# Power_supply_CAN.net
KiCad netlist of a schematic drawn in Altium Designer
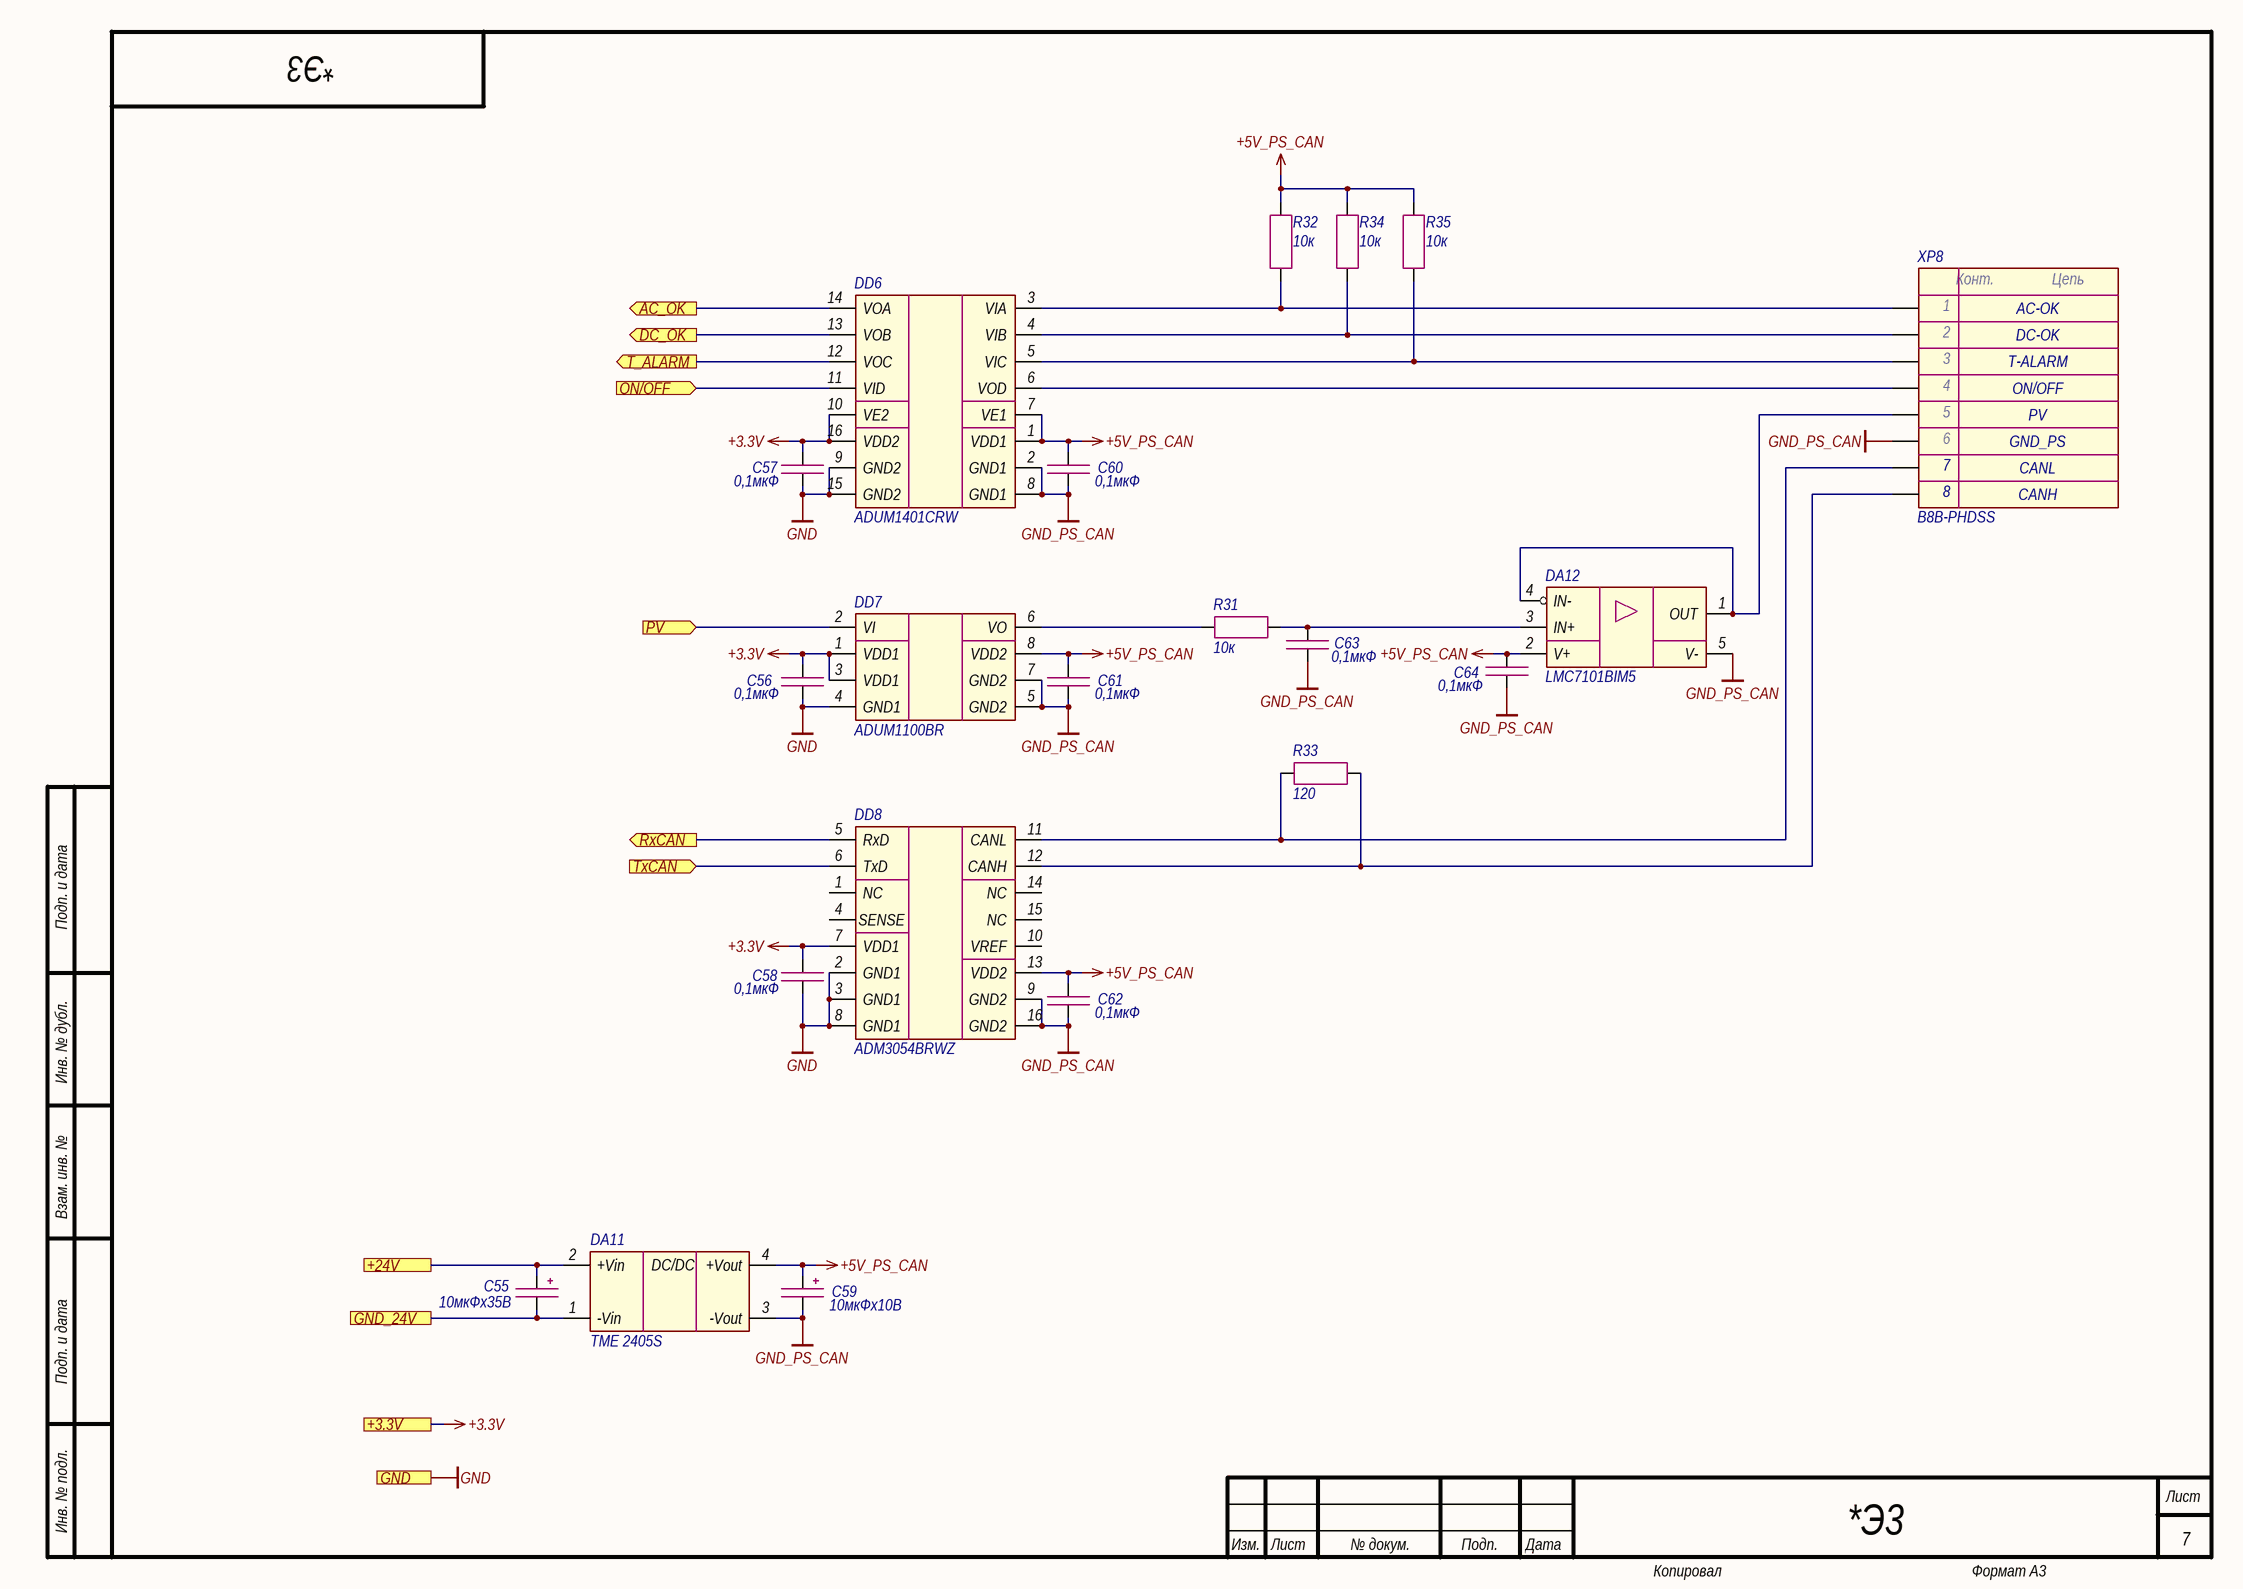
[diagram p0: Power_supply_CAN.SchDoc]

(export (version "E")
  (design (tool "Eeschema 10.0.6"))
  (components
    (comp (ref "C55")
      (value "10мкФх35B")
      (footprint "Pcb_library:CAP_C")
      (libsource (lib "Schem_library") (part "Capacitor_Polar"))
    )
    (comp (ref "C56")
      (value "0,1мкФ")
      (footprint "Pcb_library:CAP_0603")
      (fields (field (name "MANUFACTURER") "Murata"))
      (libsource (lib "Schem_library") (part "Capacitor"))
    )
    (comp (ref "C57")
      (value "0,1мкФ")
      (footprint "Pcb_library:CAP_0603")
      (fields (field (name "MANUFACTURER") "Murata"))
      (libsource (lib "Schem_library") (part "Capacitor"))
    )
    (comp (ref "C58")
      (value "0,1мкФ")
      (footprint "Pcb_library:CAP_0603")
      (fields (field (name "MANUFACTURER") "Murata"))
      (libsource (lib "Schem_library") (part "Capacitor"))
    )
    (comp (ref "C59")
      (value "10мкФх10B")
      (footprint "Pcb_library:CAP_A")
      (libsource (lib "Schem_library") (part "Capacitor_Polar"))
    )
    (comp (ref "C60")
      (value "0,1мкФ")
      (footprint "Pcb_library:CAP_0603")
      (fields (field (name "MANUFACTURER") "Murata"))
      (libsource (lib "Schem_library") (part "Capacitor"))
    )
    (comp (ref "C61")
      (value "0,1мкФ")
      (footprint "Pcb_library:CAP_0603")
      (fields (field (name "MANUFACTURER") "Murata"))
      (libsource (lib "Schem_library") (part "Capacitor"))
    )
    (comp (ref "C62")
      (value "0,1мкФ")
      (footprint "Pcb_library:CAP_0603")
      (fields (field (name "MANUFACTURER") "Murata"))
      (libsource (lib "Schem_library") (part "Capacitor"))
    )
    (comp (ref "C63")
      (value "0,1мкФ")
      (footprint "Pcb_library:CAP_0603")
      (fields (field (name "MANUFACTURER") "Murata"))
      (libsource (lib "Schem_library") (part "Capacitor"))
    )
    (comp (ref "C64")
      (value "0,1мкФ")
      (footprint "Pcb_library:CAP_0603")
      (fields (field (name "MANUFACTURER") "Murata"))
      (libsource (lib "Schem_library") (part "Capacitor"))
    )
    (comp (ref "DA11")
      (value "TME 2405S")
      (footprint "Pcb_library:TME (SIP-4)")
      (fields (field (name "MANUFACTURER") "Traco Power"))
      (libsource (lib "Schem_library") (part "TME"))
    )
    (comp (ref "DA12")
      (value "LMC7101BIM5")
      (footprint "Pcb_library:SOT-23-5")
      (fields (field (name "MANUFACTURER") "Texas Instruments"))
      (libsource (lib "Schem_library") (part "LMC7101"))
    )
    (comp (ref "DD6")
      (value "ADUM1401CRW")
      (footprint "Pcb_library:SOIC-16W")
      (fields (field (name "MANUFACTURER") "Analog Devices"))
      (libsource (lib "Schem_library") (part "ADUM1401"))
    )
    (comp (ref "DD7")
      (value "ADUM1100BR")
      (footprint "Pcb_library:SOIC-8")
      (fields (field (name "MANUFACTURER") "Analog Devices"))
      (libsource (lib "Schem_library") (part "ADUM1100"))
    )
    (comp (ref "DD8")
      (value "ADM3054BRWZ")
      (footprint "Pcb_library:SOIC-16W")
      (fields (field (name "MANUFACTURER") "Analog Devices"))
      (libsource (lib "Schem_library") (part "ADM3054BRWZ"))
    )
    (comp (ref "R31")
      (value "10к")
      (footprint "Pcb_library:RES_0603")
      (fields (field (name "MANUFACTURER") "Yageo"))
      (libsource (lib "Schem_library") (part "Resistor"))
    )
    (comp (ref "R32")
      (value "10к")
      (footprint "Pcb_library:RES_0603")
      (fields (field (name "MANUFACTURER") "Yageo"))
      (libsource (lib "Schem_library") (part "Resistor"))
    )
    (comp (ref "R33")
      (value "120")
      (footprint "Pcb_library:RES_0805")
      (fields (field (name "MANUFACTURER") "Yageo"))
      (libsource (lib "Schem_library") (part "Resistor"))
    )
    (comp (ref "R34")
      (value "10к")
      (footprint "Pcb_library:RES_0603")
      (fields (field (name "MANUFACTURER") "Yageo"))
      (libsource (lib "Schem_library") (part "Resistor"))
    )
    (comp (ref "R35")
      (value "10к")
      (footprint "Pcb_library:RES_0603")
      (fields (field (name "MANUFACTURER") "Yageo"))
      (libsource (lib "Schem_library") (part "Resistor"))
    )
    (comp (ref "XP8")
      (value "B8B-PHDSS")
      (footprint "Pcb_library:B8B-PHDSS")
      (fields (field (name "MANUFACTURER") "JST"))
      (libsource (lib "Schem_library") (part "Connector-8"))
    )
  )
  (nets
    (net (code "1") (name "+3.3V") (class "Default")
      (node (ref "C56") (pin "1") (pinfunction "1_1") (pintype "passive"))
      (node (ref "C57") (pin "1") (pinfunction "1_1") (pintype "passive"))
      (node (ref "C58") (pin "1") (pinfunction "1_1") (pintype "passive"))
      (node (ref "DD6") (pin "10") (pinfunction "VE2_10") (pintype "passive"))
      (node (ref "DD6") (pin "16") (pinfunction "VDD2_16") (pintype "passive"))
      (node (ref "DD7") (pin "1") (pinfunction "VDD1_1") (pintype "passive"))
      (node (ref "DD7") (pin "3") (pinfunction "VDD1_3") (pintype "passive"))
      (node (ref "DD8") (pin "7") (pinfunction "VDD1_7") (pintype "passive"))
    )
    (net (code "2") (name "+5V_PS_CAN") (class "Default")
      (node (ref "C59") (pin "1") (pinfunction "1_1") (pintype "passive"))
      (node (ref "C60") (pin "1") (pinfunction "1_1") (pintype "passive"))
      (node (ref "C61") (pin "1") (pinfunction "1_1") (pintype "passive"))
      (node (ref "C62") (pin "1") (pinfunction "1_1") (pintype "passive"))
      (node (ref "C64") (pin "1") (pinfunction "1_1") (pintype "passive"))
      (node (ref "DA11") (pin "4") (pinfunction "+Vout_4") (pintype "passive"))
      (node (ref "DA12") (pin "2") (pinfunction "V+_2") (pintype "passive"))
      (node (ref "DD6") (pin "1") (pinfunction "VDD1_1") (pintype "passive"))
      (node (ref "DD6") (pin "7") (pinfunction "VE1_7") (pintype "passive"))
      (node (ref "DD7") (pin "8") (pinfunction "VDD2_8") (pintype "passive"))
      (node (ref "DD8") (pin "13") (pinfunction "VDD2_13") (pintype "passive"))
      (node (ref "R32") (pin "1") (pinfunction "1_1") (pintype "passive"))
      (node (ref "R34") (pin "1") (pinfunction "1_1") (pintype "passive"))
      (node (ref "R35") (pin "1") (pinfunction "1_1") (pintype "passive"))
    )
    (net (code "3") (name "/+24V") (class "Default")
      (node (ref "C55") (pin "1") (pinfunction "1_1") (pintype "passive"))
      (node (ref "DA11") (pin "2") (pinfunction "+Vin_2") (pintype "passive"))
    )
    (net (code "4") (name "/AC_OK") (class "Default")
      (node (ref "DD6") (pin "14") (pinfunction "VOA_14") (pintype "passive"))
    )
    (net (code "5") (name "/DC_OK") (class "Default")
      (node (ref "DD6") (pin "13") (pinfunction "VOB_13") (pintype "passive"))
    )
    (net (code "6") (name "/GND_24V") (class "Default")
      (node (ref "C55") (pin "2") (pinfunction "2_2") (pintype "passive"))
      (node (ref "DA11") (pin "1") (pinfunction "-Vin_1") (pintype "passive"))
    )
    (net (code "7") (name "/ON{slash}OFF") (class "Default")
      (node (ref "DD6") (pin "11") (pinfunction "VID_11") (pintype "passive"))
    )
    (net (code "8") (name "/PV") (class "Default")
      (node (ref "DD7") (pin "2") (pinfunction "VI_2") (pintype "passive"))
    )
    (net (code "9") (name "/RxCAN") (class "Default")
      (node (ref "DD8") (pin "5") (pinfunction "RxD_5") (pintype "passive"))
    )
    (net (code "10") (name "/T_ALARM") (class "Default")
      (node (ref "DD6") (pin "12") (pinfunction "VOC_12") (pintype "passive"))
    )
    (net (code "11") (name "/TxCAN") (class "Default")
      (node (ref "DD8") (pin "6") (pinfunction "TxD_6") (pintype "passive"))
    )
    (net (code "12") (name "GND") (class "Default")
      (node (ref "C56") (pin "2") (pinfunction "2_2") (pintype "passive"))
      (node (ref "C57") (pin "2") (pinfunction "2_2") (pintype "passive"))
      (node (ref "C58") (pin "2") (pinfunction "2_2") (pintype "passive"))
      (node (ref "DD6") (pin "15") (pinfunction "GND2_15") (pintype "passive"))
      (node (ref "DD6") (pin "9") (pinfunction "GND2_9") (pintype "passive"))
      (node (ref "DD7") (pin "4") (pinfunction "GND1_4") (pintype "passive"))
      (node (ref "DD8") (pin "2") (pinfunction "GND1_2") (pintype "passive"))
      (node (ref "DD8") (pin "3") (pinfunction "GND1_3") (pintype "passive"))
      (node (ref "DD8") (pin "8") (pinfunction "GND1_8") (pintype "passive"))
    )
    (net (code "13") (name "GND_PS_CAN") (class "Default")
      (node (ref "C59") (pin "2") (pinfunction "2_2") (pintype "passive"))
      (node (ref "C60") (pin "2") (pinfunction "2_2") (pintype "passive"))
      (node (ref "C61") (pin "2") (pinfunction "2_2") (pintype "passive"))
      (node (ref "C62") (pin "2") (pinfunction "2_2") (pintype "passive"))
      (node (ref "C63") (pin "2") (pinfunction "2_2") (pintype "passive"))
      (node (ref "C64") (pin "2") (pinfunction "2_2") (pintype "passive"))
      (node (ref "DA11") (pin "3") (pinfunction "-Vout_3") (pintype "passive"))
      (node (ref "DA12") (pin "5") (pinfunction "V-_5") (pintype "passive"))
      (node (ref "DD6") (pin "2") (pinfunction "GND1_2") (pintype "passive"))
      (node (ref "DD6") (pin "8") (pinfunction "GND1_8") (pintype "passive"))
      (node (ref "DD7") (pin "5") (pinfunction "GND2_5") (pintype "passive"))
      (node (ref "DD7") (pin "7") (pinfunction "GND2_7") (pintype "passive"))
      (node (ref "DD8") (pin "16") (pinfunction "GND2_16") (pintype "passive"))
      (node (ref "DD8") (pin "9") (pinfunction "GND2_9") (pintype "passive"))
      (node (ref "XP8") (pin "6") (pintype "passive"))
    )
    (net (code "14") (name "Net-(DA12-IN+)") (class "Default")
      (node (ref "C63") (pin "1") (pinfunction "1_1") (pintype "passive"))
      (node (ref "DA12") (pin "3") (pinfunction "IN+_3") (pintype "passive"))
      (node (ref "R31") (pin "2") (pinfunction "2_2") (pintype "passive"))
    )
    (net (code "15") (name "Net-(DA12-IN-)") (class "Default")
      (node (ref "DA12") (pin "1") (pinfunction "OUT_1") (pintype "passive"))
      (node (ref "DA12") (pin "4") (pinfunction "IN-_4") (pintype "passive"))
      (node (ref "XP8") (pin "5") (pintype "passive"))
    )
    (net (code "16") (name "Net-(DD6-VIA)") (class "Default")
      (node (ref "DD6") (pin "3") (pinfunction "VIA_3") (pintype "passive"))
      (node (ref "R32") (pin "2") (pinfunction "2_2") (pintype "passive"))
      (node (ref "XP8") (pin "1") (pintype "passive"))
    )
    (net (code "17") (name "Net-(DD6-VIB)") (class "Default")
      (node (ref "DD6") (pin "4") (pinfunction "VIB_4") (pintype "passive"))
      (node (ref "R34") (pin "2") (pinfunction "2_2") (pintype "passive"))
      (node (ref "XP8") (pin "2") (pintype "passive"))
    )
    (net (code "18") (name "Net-(DD6-VIC)") (class "Default")
      (node (ref "DD6") (pin "5") (pinfunction "VIC_5") (pintype "passive"))
      (node (ref "R35") (pin "2") (pinfunction "2_2") (pintype "passive"))
      (node (ref "XP8") (pin "3") (pintype "passive"))
    )
    (net (code "19") (name "Net-(DD6-VOD)") (class "Default")
      (node (ref "DD6") (pin "6") (pinfunction "VOD_6") (pintype "passive"))
      (node (ref "XP8") (pin "4") (pintype "passive"))
    )
    (net (code "20") (name "Net-(DD7-VO)") (class "Default")
      (node (ref "DD7") (pin "6") (pinfunction "VO_6") (pintype "passive"))
      (node (ref "R31") (pin "1") (pinfunction "1_1") (pintype "passive"))
    )
    (net (code "21") (name "Net-(DD8-CANH)") (class "Default")
      (node (ref "DD8") (pin "12") (pinfunction "CANH_12") (pintype "passive"))
      (node (ref "R33") (pin "2") (pinfunction "2_2") (pintype "passive"))
      (node (ref "XP8") (pin "8") (pintype "passive"))
    )
    (net (code "22") (name "Net-(DD8-CANL)") (class "Default")
      (node (ref "DD8") (pin "11") (pinfunction "CANL_11") (pintype "passive"))
      (node (ref "R33") (pin "1") (pinfunction "1_1") (pintype "passive"))
      (node (ref "XP8") (pin "7") (pintype "passive"))
    )
    (net (code "23") (name "unconnected-(DD8-NC-Pad1)") (class "Default")
      (node (ref "DD8") (pin "1") (pinfunction "NC_1") (pintype "passive"))
    )
    (net (code "24") (name "unconnected-(DD8-NC-Pad14)") (class "Default")
      (node (ref "DD8") (pin "14") (pinfunction "NC_14") (pintype "passive"))
    )
    (net (code "25") (name "unconnected-(DD8-NC-Pad15)") (class "Default")
      (node (ref "DD8") (pin "15") (pinfunction "NC_15") (pintype "passive"))
    )
    (net (code "26") (name "unconnected-(DD8-SENSE-Pad4)") (class "Default")
      (node (ref "DD8") (pin "4") (pinfunction "SENSE_4") (pintype "passive"))
    )
    (net (code "27") (name "unconnected-(DD8-VREF-Pad10)") (class "Default")
      (node (ref "DD8") (pin "10") (pinfunction "VREF_10") (pintype "passive"))
    )
  )
)
